# MCU.net
KiCad netlist of a schematic drawn in Altium Designer
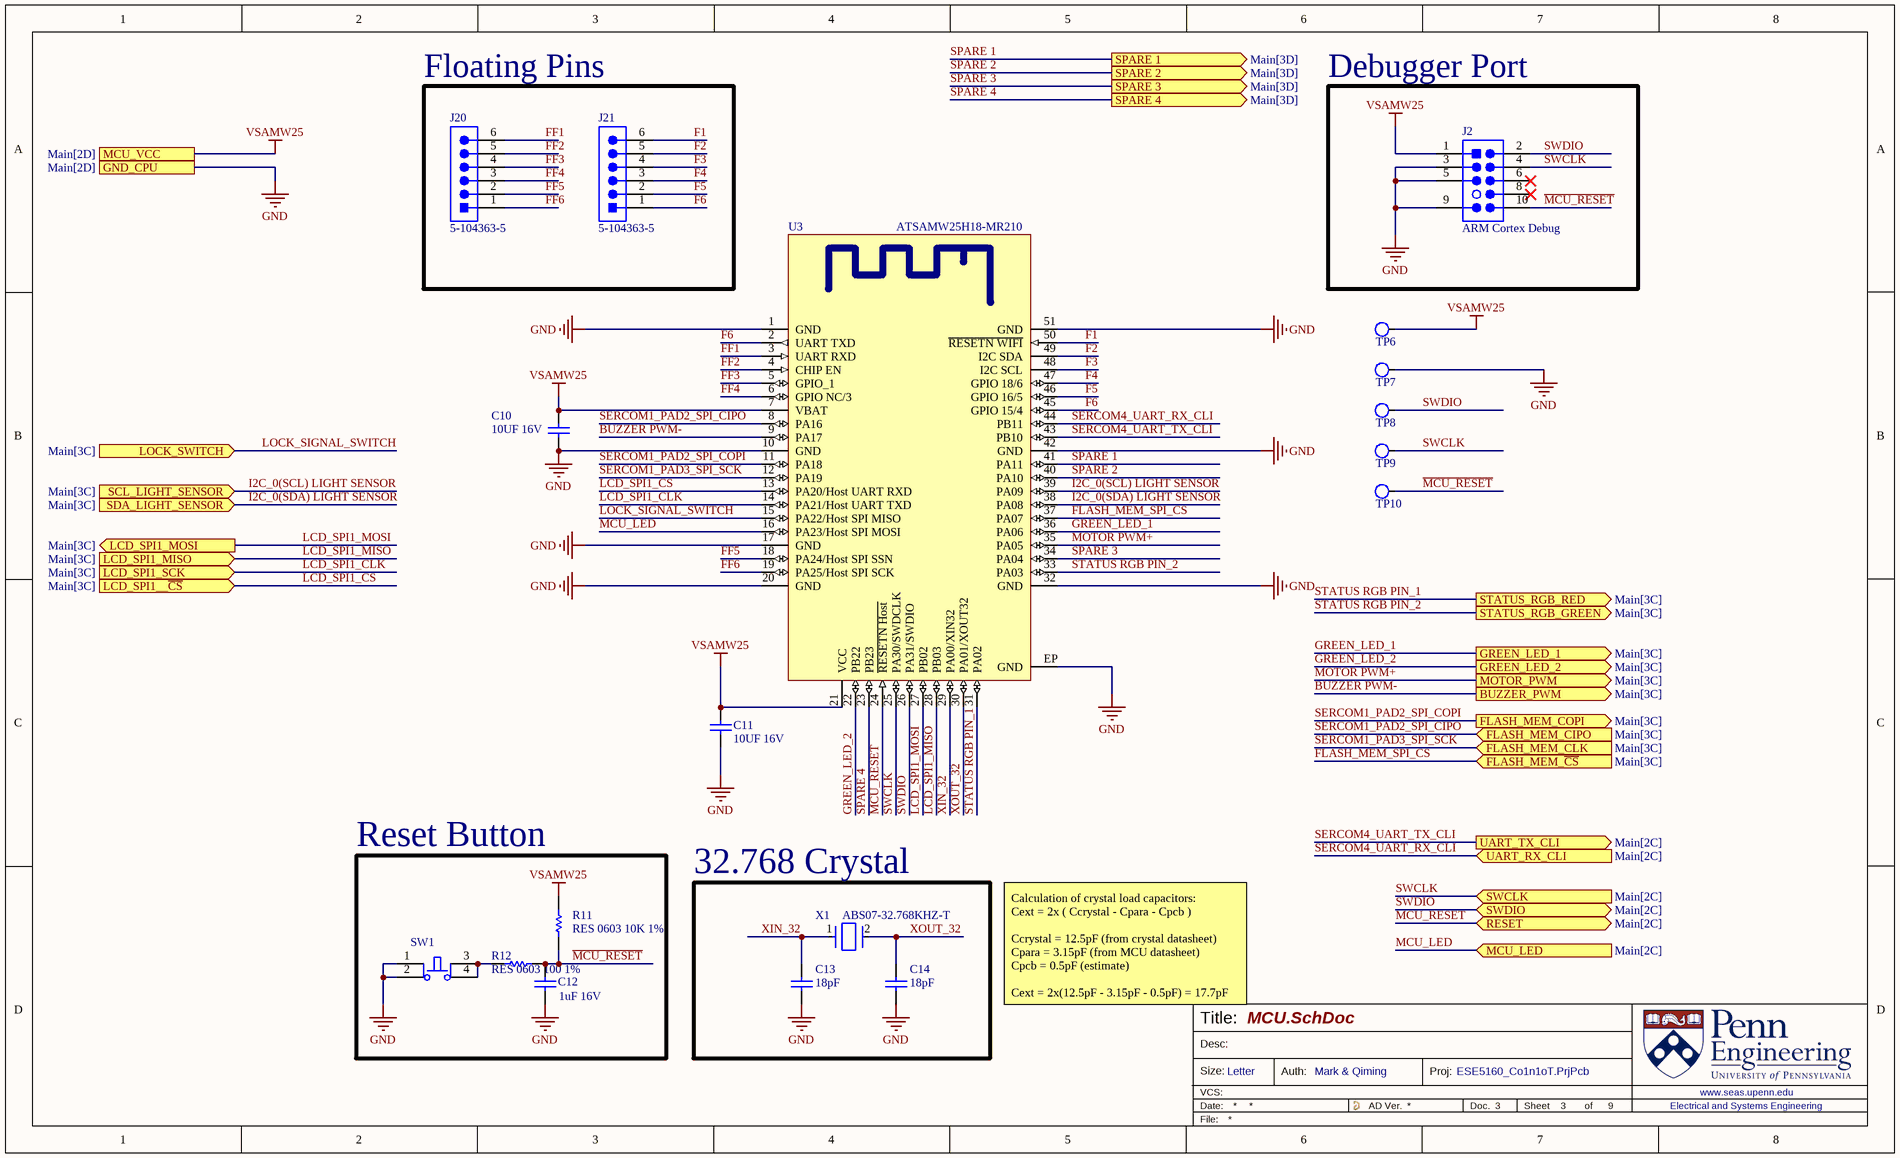
[diagram p0: MCU.SchDoc]

(export (version "E")
  (design (tool "Eeschema 10.0.6"))
  (components
    (comp (ref "C10")
      (value "10UF 16V")
      (footprint "0805_CAP_60H")
      (description "Capacitor Surface Mount 0805 Footprint 10UF 16V 20% Tolerance Ceramic X7R")
      (fields (field (name "MANUFACTURER") "Various") (field (name "TOLERANCE") "20%"))
      (libsource (lib "University of Pennsylvania (ESE Labs)") (part "cap"))
    )
    (comp (ref "C11")
      (value "10UF 16V")
      (footprint "0805_CAP_60H")
      (description "Capacitor Surface Mount 0805 Footprint 10UF 16V 20% Tolerance Ceramic X7R")
      (fields (field (name "MANUFACTURER") "Various") (field (name "TOLERANCE") "20%"))
      (libsource (lib "University of Pennsylvania (ESE Labs)") (part "cap"))
    )
    (comp (ref "C12")
      (value "1uF 16V")
      (footprint "0603_CAP")
      (description "Capacitor Surface Mount 0603 Footprint 1UF 16V 10% Tolerance Ceramic X7R")
      (fields (field (name "TOLERANCE") "10%") (field (name "MANUFACTURER") "Various"))
      (libsource (lib "University of Pennsylvania (ESE Labs)") (part "cap"))
    )
    (comp (ref "C13")
      (value "18pF")
      (footprint "0603_CAP")
      (description "Capacitor Surface Mount 0603 Footprint 18PF 50V 5% Tolerance Ceramic C0G")
      (fields (field (name "VOLTAGE") "50V") (field (name "MANUFACTURER") "Various"))
      (libsource (lib "University of Pennsylvania (ESE Labs)") (part "cap"))
    )
    (comp (ref "C14")
      (value "18pF")
      (footprint "0603_CAP")
      (description "Capacitor Surface Mount 0603 Footprint 18PF 50V 5% Tolerance Ceramic C0G")
      (fields (field (name "VOLTAGE") "50V") (field (name "MANUFACTURER") "Various"))
      (libsource (lib "University of Pennsylvania (ESE Labs)") (part "cap"))
    )
    (comp (ref "J2")
      (value "ARM Cortex Debug")
      (footprint "FTSH-105-01-F-DV-007-K PLUGIN")
      (description "10 Pin Shrouded Header, 0.050\", Key Pin 7")
      (fields (field (name "MANUFACTURER") "Samtech"))
      (libsource (lib "University of Pennsylvania (ESE Labs)") (part "Cortex Debug"))
    )
    (comp (ref "J20")
      (value "5-104363-5")
      (footprint "5-104363-5-Footprint-1")
      (libsource (lib "University of Pennsylvania (ESE)") (part "Header 1X6"))
    )
    (comp (ref "J21")
      (value "5-104363-5")
      (footprint "5-104363-5-Footprint-1")
      (libsource (lib "University of Pennsylvania (ESE)") (part "Header 1X6"))
    )
    (comp (ref "R11")
      (value "RES 0603 10K 1%")
      (footprint "0603_RES")
      (description "Resistor Surface Mount, 10K Ohms, 0603 Footprint, 1% Tolerance 0.1W")
      (fields (field (name "TOLERANCE") "1%") (field (name "MANUFACTURER") "Various"))
      (libsource (lib "University of Pennsylvania (ESE)") (part "res"))
    )
    (comp (ref "R12")
      (value "RES 0603 100 1%")
      (footprint "0603_RES")
      (description "Resistor Surface Mount, 100 Ohms, 0603 Footprint, 1% Tolerance 0.1W")
      (fields (field (name "MANUFACTURER") "Various") (field (name "TOLERANCE") "1%"))
      (libsource (lib "University of Pennsylvania (ESE)") (part "res"))
    )
    (comp (ref "SW1")
      (value "PTS810SJK250SMTRLFS")
      (footprint "PTS810SJK250SMTRLFS-Footprint-1")
      (libsource (lib "University of Pennsylvania (ESE)") (part "Tactile Switch 4 Pin"))
    )
    (comp (ref "TP6")
      (value "Testpad")
      (footprint "SMT Testpoint, 50mil")
      (description "Test Pad/Point (Testpoint, Testpad), for probing")
      (libsource (lib "University of Pennsylvania (ESE)") (part "30mm Test Pad"))
    )
    (comp (ref "TP7")
      (value "Testpad")
      (footprint "SMT Testpoint, 50mil")
      (description "Test Pad/Point (Testpoint, Testpad), for probing")
      (libsource (lib "University of Pennsylvania (ESE)") (part "30mm Test Pad"))
    )
    (comp (ref "TP8")
      (value "Testpad")
      (footprint "SMT Testpoint, 50mil")
      (description "Test Pad/Point (Testpoint, Testpad), for probing")
      (libsource (lib "University of Pennsylvania (ESE)") (part "30mm Test Pad"))
    )
    (comp (ref "TP9")
      (value "Testpad")
      (footprint "SMT Testpoint, 50mil")
      (description "Test Pad/Point (Testpoint, Testpad), for probing")
      (libsource (lib "University of Pennsylvania (ESE)") (part "30mm Test Pad"))
    )
    (comp (ref "TP10")
      (value "Testpad")
      (footprint "SMT Testpoint, 50mil")
      (description "Test Pad/Point (Testpoint, Testpad), for probing")
      (libsource (lib "University of Pennsylvania (ESE)") (part "30mm Test Pad"))
    )
    (comp (ref "U3")
      (value "ATSAMW25H18-MR210")
      (footprint "ATSAMW25H18-MR210-Footprint-1")
      (libsource (lib "University of Pennsylvania (ESE Labs)") (part "ATSAMW25H18-MR210-Symbol-1"))
    )
    (comp (ref "X1")
      (value "ABS07-32.768KHZ-T")
      (footprint "FP-ABS07-MFG")
      (description "Crystal 32.768kHz ±20ppm (Tol) 12.5pF FUND 70kΩ 2-Pin CSMD T/R")
      (fields (field (name "TOLERANCE") "20ppm"))
      (libsource (lib "Altium Content Vault") (part "c23a69dc6c9e2f18f2079038eb95dd1"))
    )
  )
  (nets
    (net (code "1") (name "/BUZZER PWM-") (class "Default")
      (node (ref "U3") (pin "9") (pinfunction "PA17_9") (pintype "bidirectional"))
    )
    (net (code "2") (name "/F1") (class "Default")
      (node (ref "J21") (pin "6") (pinfunction "6_6") (pintype "passive"))
      (node (ref "U3") (pin "50") (pinfunction "~{RESETN_WIFI}_50") (pintype "input"))
    )
    (net (code "3") (name "/F2") (class "Default")
      (node (ref "J21") (pin "5") (pinfunction "5_5") (pintype "passive"))
      (node (ref "U3") (pin "49") (pinfunction "I2C_SDA_49") (pintype "open_collector"))
    )
    (net (code "4") (name "/F3") (class "Default")
      (node (ref "J21") (pin "4") (pinfunction "4_4") (pintype "passive"))
      (node (ref "U3") (pin "48") (pinfunction "I2C_SCL_48") (pintype "open_collector"))
    )
    (net (code "5") (name "/F4") (class "Default")
      (node (ref "J21") (pin "3") (pinfunction "3_3") (pintype "passive"))
      (node (ref "U3") (pin "47") (pinfunction "GPIO_18/6_47") (pintype "bidirectional"))
    )
    (net (code "6") (name "/F5") (class "Default")
      (node (ref "J21") (pin "2") (pinfunction "2_2") (pintype "passive"))
      (node (ref "U3") (pin "46") (pinfunction "GPIO_16/5_46") (pintype "bidirectional"))
    )
    (net (code "7") (name "/F6") (class "Default")
      (node (ref "J21") (pin "1") (pinfunction "1_1") (pintype "passive"))
      (node (ref "U3") (pin "2") (pinfunction "UART_TXD_2") (pintype "output"))
      (node (ref "U3") (pin "45") (pinfunction "GPIO_15/4_45") (pintype "bidirectional"))
    )
    (net (code "8") (name "/FF1") (class "Default")
      (node (ref "J20") (pin "6") (pinfunction "6_6") (pintype "passive"))
      (node (ref "U3") (pin "3") (pinfunction "UART_RXD_3") (pintype "input"))
    )
    (net (code "9") (name "/FF2") (class "Default")
      (node (ref "J20") (pin "5") (pinfunction "5_5") (pintype "passive"))
      (node (ref "U3") (pin "4") (pinfunction "CHIP_EN_4") (pintype "input"))
    )
    (net (code "10") (name "/FF3") (class "Default")
      (node (ref "J20") (pin "4") (pinfunction "4_4") (pintype "passive"))
      (node (ref "U3") (pin "5") (pinfunction "GPIO_1_5") (pintype "bidirectional"))
    )
    (net (code "11") (name "/FF4") (class "Default")
      (node (ref "J20") (pin "3") (pinfunction "3_3") (pintype "passive"))
      (node (ref "U3") (pin "6") (pinfunction "GPIO_NC/3_6") (pintype "bidirectional"))
    )
    (net (code "12") (name "/FF5") (class "Default")
      (node (ref "J20") (pin "2") (pinfunction "2_2") (pintype "passive"))
      (node (ref "U3") (pin "18") (pinfunction "PA24/Host_SPI_SSN_18") (pintype "bidirectional"))
    )
    (net (code "13") (name "/FF6") (class "Default")
      (node (ref "J20") (pin "1") (pinfunction "1_1") (pintype "passive"))
      (node (ref "U3") (pin "19") (pinfunction "PA25/Host_SPI_SCK_19") (pintype "bidirectional"))
    )
    (net (code "14") (name "/FLASH_MEM_SPI_~{CS}") (class "Default")
      (node (ref "U3") (pin "37") (pinfunction "PA07_37") (pintype "bidirectional"))
    )
    (net (code "15") (name "/GREEN_LED_1") (class "Default")
      (node (ref "U3") (pin "36") (pinfunction "PA06_36") (pintype "bidirectional"))
    )
    (net (code "16") (name "/GREEN_LED_2") (class "Default")
      (node (ref "U3") (pin "22") (pinfunction "PB22_22") (pintype "bidirectional"))
    )
    (net (code "17") (name "/I2C_0(SCL) LIGHT SENSOR") (class "Default")
      (node (ref "U3") (pin "39") (pinfunction "PA09_39") (pintype "bidirectional"))
    )
    (net (code "18") (name "/I2C_0(SDA) LIGHT SENSOR") (class "Default")
      (node (ref "U3") (pin "38") (pinfunction "PA08_38") (pintype "bidirectional"))
    )
    (net (code "19") (name "/LCD_SPI1_CLK") (class "Default")
      (node (ref "U3") (pin "14") (pinfunction "PA21/Host_UART_TXD_14") (pintype "bidirectional"))
    )
    (net (code "20") (name "/LCD_SPI1_MISO") (class "Default")
      (node (ref "U3") (pin "28") (pinfunction "PB03_28") (pintype "bidirectional"))
    )
    (net (code "21") (name "/LCD_SPI1_MOSI") (class "Default")
      (node (ref "U3") (pin "27") (pinfunction "PB02_27") (pintype "bidirectional"))
    )
    (net (code "22") (name "/LCD_SPI1_~{CS}") (class "Default")
      (node (ref "U3") (pin "13") (pinfunction "PA20/Host_UART_RXD_13") (pintype "bidirectional"))
    )
    (net (code "23") (name "/LOCK_SIGNAL_SWITCH") (class "Default")
      (node (ref "U3") (pin "15") (pinfunction "PA22/Host_SPI_MISO_15") (pintype "bidirectional"))
    )
    (net (code "24") (name "/MCU_LED") (class "Default")
      (node (ref "U3") (pin "16") (pinfunction "PA23/Host_SPI_MOSI_16") (pintype "bidirectional"))
    )
    (net (code "26") (name "/MOTOR PWM+") (class "Default")
      (node (ref "U3") (pin "35") (pinfunction "PA05_35") (pintype "bidirectional"))
    )
    (net (code "27") (name "/SERCOM1_PAD2_SPI_CIPO") (class "Default")
      (node (ref "U3") (pin "8") (pinfunction "PA16_8") (pintype "bidirectional"))
    )
    (net (code "28") (name "/SERCOM1_PAD2_SPI_COPI") (class "Default")
      (node (ref "U3") (pin "11") (pinfunction "PA18_11") (pintype "bidirectional"))
    )
    (net (code "29") (name "/SERCOM1_PAD3_SPI_SCK") (class "Default")
      (node (ref "U3") (pin "12") (pinfunction "PA19_12") (pintype "bidirectional"))
    )
    (net (code "30") (name "/SERCOM4_UART_RX_CLI") (class "Default")
      (node (ref "U3") (pin "44") (pinfunction "PB11_44") (pintype "bidirectional"))
    )
    (net (code "31") (name "/SERCOM4_UART_TX_CLI") (class "Default")
      (node (ref "U3") (pin "43") (pinfunction "PB10_43") (pintype "bidirectional"))
    )
    (net (code "32") (name "/SPARE 1") (class "Default")
      (node (ref "U3") (pin "41") (pinfunction "PA11_41") (pintype "bidirectional"))
    )
    (net (code "33") (name "/SPARE 2") (class "Default")
      (node (ref "U3") (pin "40") (pinfunction "PA10_40") (pintype "bidirectional"))
    )
    (net (code "34") (name "/SPARE 3") (class "Default")
      (node (ref "U3") (pin "34") (pinfunction "PA04_34") (pintype "bidirectional"))
    )
    (net (code "35") (name "/SPARE 4") (class "Default")
      (node (ref "U3") (pin "23") (pinfunction "PB23_23") (pintype "bidirectional"))
    )
    (net (code "36") (name "/STATUS RGB PIN_1") (class "Default")
      (node (ref "U3") (pin "31") (pinfunction "PA02_31") (pintype "bidirectional"))
    )
    (net (code "37") (name "/STATUS RGB PIN_2") (class "Default")
      (node (ref "U3") (pin "33") (pinfunction "PA03_33") (pintype "bidirectional"))
    )
    (net (code "38") (name "/SWCLK") (class "Default")
      (node (ref "J2") (pin "4") (pinfunction "4_4") (pintype "passive"))
      (node (ref "TP9") (pin "1") (pinfunction "1_1") (pintype "passive"))
      (node (ref "U3") (pin "25") (pinfunction "PA30/SWDCLK_25") (pintype "bidirectional"))
    )
    (net (code "39") (name "/SWDIO") (class "Default")
      (node (ref "J2") (pin "2") (pinfunction "2_2") (pintype "passive"))
      (node (ref "TP8") (pin "1") (pinfunction "1_1") (pintype "passive"))
      (node (ref "U3") (pin "26") (pinfunction "PA31/SWDIO_26") (pintype "bidirectional"))
    )
    (net (code "40") (name "/XIN_32") (class "Default")
      (node (ref "C13") (pin "2") (pinfunction "2_2") (pintype "passive"))
      (node (ref "U3") (pin "29") (pinfunction "PA00/XIN32_29") (pintype "bidirectional"))
      (node (ref "X1") (pin "1") (pinfunction "1_1") (pintype "passive"))
    )
    (net (code "41") (name "/XOUT_32") (class "Default")
      (node (ref "C14") (pin "2") (pinfunction "2_2") (pintype "passive"))
      (node (ref "U3") (pin "30") (pinfunction "PA01/XOUT32_30") (pintype "bidirectional"))
      (node (ref "X1") (pin "2") (pinfunction "2_2") (pintype "passive"))
    )
    (net (code "42") (name "/~{MCU_RESET}") (class "Default")
      (node (ref "C12") (pin "2") (pinfunction "2_2") (pintype "passive"))
      (node (ref "J2") (pin "10") (pinfunction "10_10") (pintype "passive"))
      (node (ref "R11") (pin "1") (pinfunction "1_1") (pintype "passive"))
      (node (ref "R12") (pin "2") (pinfunction "2_2") (pintype "passive"))
      (node (ref "TP10") (pin "1") (pinfunction "1_1") (pintype "passive"))
      (node (ref "U3") (pin "24") (pinfunction "~{RESETN_Host}_24") (pintype "input"))
    )
    (net (code "43") (name "GND") (class "Default")
      (node (ref "C10") (pin "1") (pinfunction "1_1") (pintype "passive"))
      (node (ref "C11") (pin "2") (pinfunction "2_2") (pintype "passive"))
      (node (ref "C12") (pin "1") (pinfunction "1_1") (pintype "passive"))
      (node (ref "C13") (pin "1") (pinfunction "1_1") (pintype "passive"))
      (node (ref "C14") (pin "1") (pinfunction "1_1") (pintype "passive"))
      (node (ref "J2") (pin "3") (pinfunction "3_3") (pintype "power_in"))
      (node (ref "J2") (pin "5") (pinfunction "5_5") (pintype "power_in"))
      (node (ref "J2") (pin "9") (pinfunction "9_9") (pintype "passive"))
      (node (ref "SW1") (pin "1") (pinfunction "1_1") (pintype "passive"))
      (node (ref "SW1") (pin "2") (pinfunction "2_2") (pintype "passive"))
      (node (ref "TP7") (pin "1") (pinfunction "1_1") (pintype "passive"))
      (node (ref "U3") (pin "1") (pinfunction "GND_1") (pintype "power_in"))
      (node (ref "U3") (pin "10") (pinfunction "GND_10") (pintype "power_in"))
      (node (ref "U3") (pin "17") (pinfunction "GND_17") (pintype "power_in"))
      (node (ref "U3") (pin "20") (pinfunction "GND_20") (pintype "power_in"))
      (node (ref "U3") (pin "32") (pinfunction "GND_32") (pintype "power_in"))
      (node (ref "U3") (pin "42") (pinfunction "GND_42") (pintype "power_in"))
      (node (ref "U3") (pin "51") (pinfunction "GND_51") (pintype "power_in"))
      (node (ref "U3") (pin "EP") (pinfunction "GND_EP") (pintype "power_in"))
    )
    (net (code "44") (name "Net-(R12-Pad1)") (class "Default")
      (node (ref "R12") (pin "1") (pinfunction "1_1") (pintype "passive"))
      (node (ref "SW1") (pin "3") (pinfunction "2_3") (pintype "passive"))
      (node (ref "SW1") (pin "4") (pinfunction "4_4") (pintype "passive"))
    )
    (net (code "45") (name "VSAMW25") (class "Default")
      (node (ref "C10") (pin "2") (pinfunction "2_2") (pintype "passive"))
      (node (ref "C11") (pin "1") (pinfunction "1_1") (pintype "passive"))
      (node (ref "J2") (pin "1") (pinfunction "1_1") (pintype "power_in"))
      (node (ref "R11") (pin "2") (pinfunction "2_2") (pintype "passive"))
      (node (ref "TP6") (pin "1") (pinfunction "1_1") (pintype "passive"))
      (node (ref "U3") (pin "21") (pinfunction "VCC_21") (pintype "power_in"))
      (node (ref "U3") (pin "7") (pinfunction "VBAT_7") (pintype "power_in"))
    )
    (net (code "46") (name "unconnected-(J2-Pad6)") (class "Default")
      (node (ref "J2") (pin "6") (pinfunction "6_6") (pintype "passive+no_connect"))
    )
    (net (code "47") (name "unconnected-(J2-Pad8)") (class "Default")
      (node (ref "J2") (pin "8") (pinfunction "8_8") (pintype "passive+no_connect"))
    )
  )
)
